# MOD_VIBRACION.net
KiCad netlist of a schematic drawn in Altium Designer
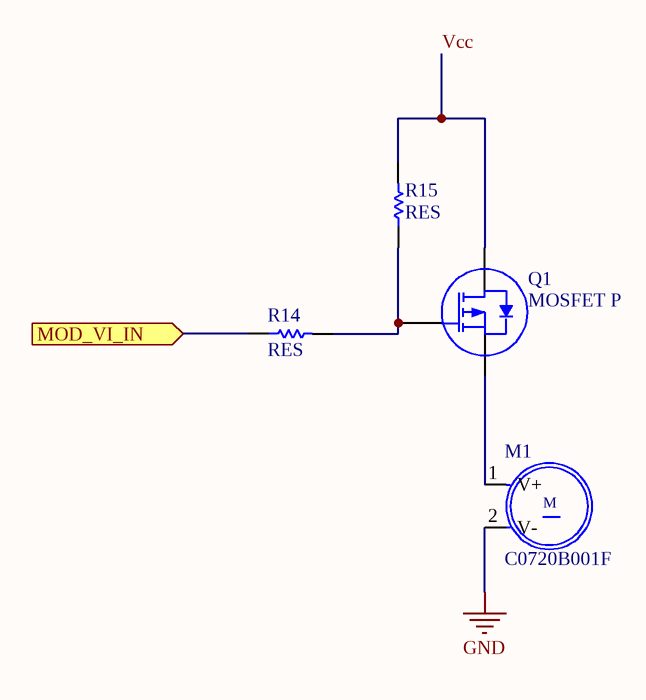
[diagram p0: MOD_VIBRACION.SchDoc]

(export (version "E")
  (design (tool "Eeschema 10.0.6"))
  (components
    (comp (ref "M1")
      (value "C0720B001F")
      (footprint "XDCR_C0720B001F")
      (description "DC Motor Vibration, ERM 10000 RPM 3VDC")
      (fields (field (name "MF") "Jinlong Machinery"))
      (libsource (lib "C0720B001F") (part "C0720B001F"))
    )
    (comp (ref "Q1") (value "MOSFET P") (footprint "SOT23") (libsource (lib "LIBEBAL") (part "MOSFET P")))
    (comp (ref "R14") (value "RES") (footprint "0805") (libsource (lib "LIBEBAL") (part "RES")))
    (comp (ref "R15") (value "RES") (footprint "0805") (libsource (lib "LIBEBAL") (part "RES")))
  )
  (nets
    (net (code "1") (name "/MOD_VI_IN") (class "Default")
      (node (ref "R14") (pin "1") (pinfunction "1_1") (pintype "passive"))
    )
    (net (code "2") (name "/Vcc") (class "Default")
      (node (ref "Q1") (pin "2") (pinfunction "D_2") (pintype "passive"))
      (node (ref "R15") (pin "2") (pinfunction "2_2") (pintype "passive"))
    )
    (net (code "3") (name "GND") (class "Default")
      (node (ref "M1") (pin "2") (pinfunction "V-_2") (pintype "power_in"))
    )
    (net (code "4") (name "Net-(M1-V+)") (class "Default")
      (node (ref "M1") (pin "1") (pinfunction "V+_1") (pintype "power_in"))
      (node (ref "Q1") (pin "3") (pinfunction "S_3") (pintype "passive"))
    )
    (net (code "5") (name "Net-(Q1-G)") (class "Default")
      (node (ref "Q1") (pin "1") (pinfunction "G_1") (pintype "passive"))
      (node (ref "R14") (pin "2") (pinfunction "2_2") (pintype "passive"))
      (node (ref "R15") (pin "1") (pinfunction "1_1") (pintype "passive"))
    )
  )
)
